# Petra_1.net
KiCad netlist of a schematic drawn in EAGLE
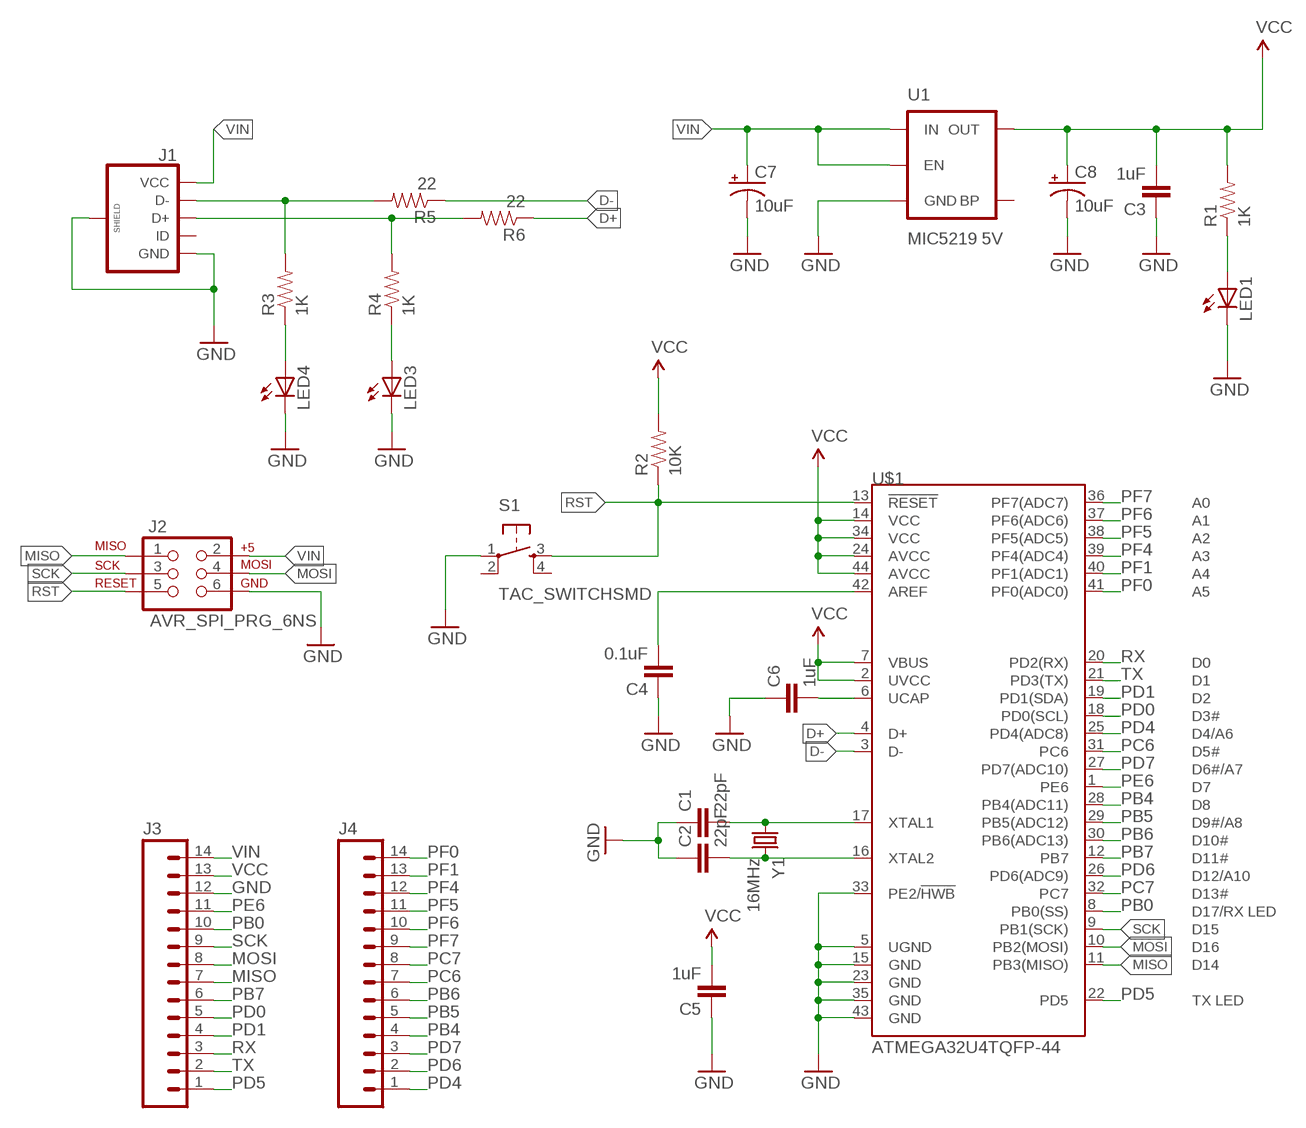
[diagram p0: schematic, sheet 1]

(export (version "E")
  (design (tool "Eeschema 10.0.6"))
  (components
    (comp (ref "C1")
      (value "22pF")
      (footprint "eagle-import:0402-CAP")
      (libsource (lib "eagle-import") (part "CAP0402-CAP"))
    )
    (comp (ref "C2")
      (value "22pF")
      (footprint "eagle-import:0402-CAP")
      (libsource (lib "eagle-import") (part "CAP0402-CAP"))
    )
    (comp (ref "C3")
      (value "1uF")
      (footprint "eagle-import:0402-CAP")
      (libsource (lib "eagle-import") (part "CAP0402-CAP"))
    )
    (comp (ref "C4")
      (value "0.1uF")
      (footprint "eagle-import:0402-CAP")
      (libsource (lib "eagle-import") (part "CAP0402-CAP"))
    )
    (comp (ref "C5")
      (value "1uF")
      (footprint "eagle-import:0402-CAP")
      (libsource (lib "eagle-import") (part "CAP0402-CAP"))
    )
    (comp (ref "C6")
      (value "1uF")
      (footprint "eagle-import:0402-CAP")
      (libsource (lib "eagle-import") (part "CAP0402-CAP"))
    )
    (comp (ref "C7")
      (value "10uF")
      (footprint "eagle-import:EIA3216")
      (libsource (lib "eagle-import") (part "CAP_POL1206"))
    )
    (comp (ref "C8")
      (value "10uF")
      (footprint "eagle-import:EIA3216")
      (libsource (lib "eagle-import") (part "CAP_POL1206"))
    )
    (comp (ref "J1")
      (value "USB_MICROB_PLUGCONN-11752")
      (footprint "eagle-import:USB-B-MICRO-SMD_V03")
      (libsource (lib "eagle-import") (part "USB_MICROB_PLUGCONN-11752"))
    )
    (comp (ref "J2")
      (value "AVR_SPI_PRG_6NS")
      (footprint "eagle-import:2X3-NS")
      (libsource (lib "eagle-import") (part "AVR_SPI_PRG_6NS"))
    )
    (comp (ref "J3")
      (value "M14")
      (footprint "eagle-import:1X14")
      (libsource (lib "eagle-import") (part "M14"))
    )
    (comp (ref "J4")
      (value "M14")
      (footprint "eagle-import:1X14")
      (libsource (lib "eagle-import") (part "M14"))
    )
    (comp (ref "LED1")
      (value "LEDCHIP-LED0805")
      (footprint "eagle-import:CHIP-LED0805")
      (libsource (lib "eagle-import") (part "LEDCHIP-LED0805"))
    )
    (comp (ref "LED3")
      (value "LEDCHIP-LED0805")
      (footprint "eagle-import:CHIP-LED0805")
      (libsource (lib "eagle-import") (part "LEDCHIP-LED0805"))
    )
    (comp (ref "LED4")
      (value "LEDCHIP-LED0805")
      (footprint "eagle-import:CHIP-LED0805")
      (libsource (lib "eagle-import") (part "LEDCHIP-LED0805"))
    )
    (comp (ref "R1")
      (value "1K")
      (footprint "eagle-import:0603-RES")
      (libsource (lib "eagle-import") (part "10KOHM-1/10W-1%(0603)0603"))
    )
    (comp (ref "R2")
      (value "10K")
      (footprint "eagle-import:0603-RES")
      (libsource (lib "eagle-import") (part "10KOHM-1/10W-1%(0603)0603"))
    )
    (comp (ref "R3")
      (value "1K")
      (footprint "eagle-import:0603-RES")
      (libsource (lib "eagle-import") (part "10KOHM-1/10W-1%(0603)0603"))
    )
    (comp (ref "R4")
      (value "1K")
      (footprint "eagle-import:0603-RES")
      (libsource (lib "eagle-import") (part "10KOHM-1/10W-1%(0603)0603"))
    )
    (comp (ref "R5")
      (value "22")
      (footprint "eagle-import:0603-RES")
      (libsource (lib "eagle-import") (part "10KOHM-1/10W-1%(0603)0603"))
    )
    (comp (ref "R6")
      (value "22")
      (footprint "eagle-import:0603-RES")
      (libsource (lib "eagle-import") (part "10KOHM-1/10W-1%(0603)0603"))
    )
    (comp (ref "S1")
      (value "TAC_SWITCHSMD")
      (footprint "eagle-import:TACTILE-SWITCH-SMD")
      (libsource (lib "eagle-import") (part "TAC_SWITCHSMD"))
    )
    (comp (ref "U$1")
      (value "ATMEGA32U4TQFP-44")
      (footprint "eagle-import:TQFP44")
      (libsource (lib "eagle-import") (part "ATMEGA32U4TQFP-44"))
    )
    (comp (ref "U1")
      (value "MIC5219 5V")
      (footprint "eagle-import:SOT23-5")
      (libsource (lib "eagle-import") (part "V_REG_MIC52195V"))
    )
    (comp (ref "Y1")
      (value "16MHz")
      (footprint "eagle-import:CRYSTAL-SMD-5X3")
      (libsource (lib "eagle-import") (part "CRYSTALCRYSTAL-SMD-5X3-16MHZ"))
    )
  )
  (nets
    (net (code "1") (name "/PB0") (class "Default")
      (node (ref "J3") (pin "10") (pinfunction "10_10") (pintype "passive"))
      (node (ref "U$1") (pin "8") (pinfunction "PB0(SS)_8") (pintype "bidirectional"))
    )
    (net (code "2") (name "/PB4") (class "Default")
      (node (ref "J4") (pin "4") (pinfunction "4_4") (pintype "passive"))
      (node (ref "U$1") (pin "28") (pinfunction "PB4(ADC11)_28") (pintype "bidirectional"))
    )
    (net (code "3") (name "/PB5") (class "Default")
      (node (ref "J4") (pin "5") (pinfunction "5_5") (pintype "passive"))
      (node (ref "U$1") (pin "29") (pinfunction "PB5(ADC12)_29") (pintype "bidirectional"))
    )
    (net (code "4") (name "/PB6") (class "Default")
      (node (ref "J4") (pin "6") (pinfunction "6_6") (pintype "passive"))
      (node (ref "U$1") (pin "30") (pinfunction "PB6(ADC13)_30") (pintype "bidirectional"))
    )
    (net (code "5") (name "/PB7") (class "Default")
      (node (ref "J3") (pin "6") (pinfunction "6_6") (pintype "passive"))
      (node (ref "U$1") (pin "12") (pinfunction "PB7_12") (pintype "bidirectional"))
    )
    (net (code "6") (name "/PC6") (class "Default")
      (node (ref "J4") (pin "7") (pinfunction "7_7") (pintype "passive"))
      (node (ref "U$1") (pin "31") (pinfunction "PC6_31") (pintype "bidirectional"))
    )
    (net (code "7") (name "/PC7") (class "Default")
      (node (ref "J4") (pin "8") (pinfunction "8_8") (pintype "passive"))
      (node (ref "U$1") (pin "32") (pinfunction "PC7_32") (pintype "bidirectional"))
    )
    (net (code "8") (name "/PD0") (class "Default")
      (node (ref "J3") (pin "5") (pinfunction "5_5") (pintype "passive"))
      (node (ref "U$1") (pin "18") (pinfunction "PD0(SCL)_18") (pintype "bidirectional"))
    )
    (net (code "9") (name "/PD1") (class "Default")
      (node (ref "J3") (pin "4") (pinfunction "4_4") (pintype "passive"))
      (node (ref "U$1") (pin "19") (pinfunction "PD1(SDA)_19") (pintype "bidirectional"))
    )
    (net (code "10") (name "/PD4") (class "Default")
      (node (ref "J4") (pin "1") (pinfunction "1_1") (pintype "passive"))
      (node (ref "U$1") (pin "25") (pinfunction "PD4(ADC8)_25") (pintype "bidirectional"))
    )
    (net (code "11") (name "/PD5") (class "Default")
      (node (ref "J3") (pin "1") (pinfunction "1_1") (pintype "passive"))
      (node (ref "U$1") (pin "22") (pinfunction "PD5_22") (pintype "bidirectional"))
    )
    (net (code "12") (name "/PD6") (class "Default")
      (node (ref "J4") (pin "2") (pinfunction "2_2") (pintype "passive"))
      (node (ref "U$1") (pin "26") (pinfunction "PD6(ADC9)_26") (pintype "bidirectional"))
    )
    (net (code "13") (name "/PD7") (class "Default")
      (node (ref "J4") (pin "3") (pinfunction "3_3") (pintype "passive"))
      (node (ref "U$1") (pin "27") (pinfunction "PD7(ADC10)_27") (pintype "bidirectional"))
    )
    (net (code "14") (name "/PE6") (class "Default")
      (node (ref "J3") (pin "11") (pinfunction "11_11") (pintype "passive"))
      (node (ref "U$1") (pin "1") (pinfunction "PE6_1") (pintype "bidirectional"))
    )
    (net (code "15") (name "/PF0") (class "Default")
      (node (ref "J4") (pin "14") (pinfunction "14_14") (pintype "passive"))
      (node (ref "U$1") (pin "41") (pinfunction "PF0(ADC0)_41") (pintype "bidirectional"))
    )
    (net (code "16") (name "/PF1") (class "Default")
      (node (ref "J4") (pin "13") (pinfunction "13_13") (pintype "passive"))
      (node (ref "U$1") (pin "40") (pinfunction "PF1(ADC1)_40") (pintype "bidirectional"))
    )
    (net (code "17") (name "/PF4") (class "Default")
      (node (ref "J4") (pin "12") (pinfunction "12_12") (pintype "passive"))
      (node (ref "U$1") (pin "39") (pinfunction "PF4(ADC4)_39") (pintype "bidirectional"))
    )
    (net (code "18") (name "/PF5") (class "Default")
      (node (ref "J4") (pin "11") (pinfunction "11_11") (pintype "passive"))
      (node (ref "U$1") (pin "38") (pinfunction "PF5(ADC5)_38") (pintype "bidirectional"))
    )
    (net (code "19") (name "/PF6") (class "Default")
      (node (ref "J4") (pin "10") (pinfunction "10_10") (pintype "passive"))
      (node (ref "U$1") (pin "37") (pinfunction "PF6(ADC6)_37") (pintype "bidirectional"))
    )
    (net (code "20") (name "/PF7") (class "Default")
      (node (ref "J4") (pin "9") (pinfunction "9_9") (pintype "passive"))
      (node (ref "U$1") (pin "36") (pinfunction "PF7(ADC7)_36") (pintype "bidirectional"))
    )
    (net (code "21") (name "/RX") (class "Default")
      (node (ref "J3") (pin "3") (pinfunction "3_3") (pintype "passive"))
      (node (ref "U$1") (pin "20") (pinfunction "PD2(RX)_20") (pintype "bidirectional"))
    )
    (net (code "22") (name "/TX") (class "Default")
      (node (ref "J3") (pin "2") (pinfunction "2_2") (pintype "passive"))
      (node (ref "U$1") (pin "21") (pinfunction "PD3(TX)_21") (pintype "bidirectional"))
    )
    (net (code "23") (name "D+") (class "Default")
      (node (ref "R6") (pin "1") (pinfunction "1_1") (pintype "passive"))
      (node (ref "U$1") (pin "4") (pinfunction "D+_4") (pintype "bidirectional"))
    )
    (net (code "24") (name "D-") (class "Default")
      (node (ref "R5") (pin "1") (pinfunction "1_1") (pintype "passive"))
      (node (ref "U$1") (pin "3") (pinfunction "D-_3") (pintype "bidirectional"))
    )
    (net (code "25") (name "GND") (class "Default")
      (node (ref "C1") (pin "1") (pinfunction "1_1") (pintype "passive"))
      (node (ref "C2") (pin "1") (pinfunction "1_1") (pintype "passive"))
      (node (ref "C3") (pin "1") (pinfunction "1_1") (pintype "passive"))
      (node (ref "C4") (pin "1") (pinfunction "1_1") (pintype "passive"))
      (node (ref "C5") (pin "1") (pinfunction "1_1") (pintype "passive"))
      (node (ref "C6") (pin "1") (pinfunction "1_1") (pintype "passive"))
      (node (ref "C7") (pin "C") (pinfunction "-_C") (pintype "passive"))
      (node (ref "C8") (pin "C") (pinfunction "-_C") (pintype "passive"))
      (node (ref "J1") (pin "GND") (pinfunction "GND_GND") (pintype "bidirectional"))
      (node (ref "J1") (pin "SHIELD1") (pinfunction "SHIELD_SHIELD1") (pintype "bidirectional"))
      (node (ref "J1") (pin "SHIELD2") (pinfunction "SHIELD_SHIELD2") (pintype "bidirectional"))
      (node (ref "J1") (pin "SHIELD3") (pinfunction "SHIELD_SHIELD3") (pintype "bidirectional"))
      (node (ref "J2") (pin "6") (pinfunction "6_6") (pintype "passive"))
      (node (ref "J3") (pin "12") (pinfunction "12_12") (pintype "passive"))
      (node (ref "LED1") (pin "C") (pinfunction "C_C") (pintype "passive"))
      (node (ref "LED3") (pin "C") (pinfunction "C_C") (pintype "passive"))
      (node (ref "LED4") (pin "C") (pinfunction "C_C") (pintype "passive"))
      (node (ref "S1") (pin "1") (pinfunction "1_1") (pintype "passive"))
      (node (ref "U$1") (pin "15") (pinfunction "GND_15") (pintype "bidirectional"))
      (node (ref "U$1") (pin "23") (pinfunction "GND_23") (pintype "bidirectional"))
      (node (ref "U$1") (pin "33") (pinfunction "PE2/~{HWB}_33") (pintype "bidirectional"))
      (node (ref "U$1") (pin "35") (pinfunction "GND_35") (pintype "bidirectional"))
      (node (ref "U$1") (pin "43") (pinfunction "GND_43") (pintype "bidirectional"))
      (node (ref "U$1") (pin "5") (pinfunction "UGND_5") (pintype "bidirectional"))
      (node (ref "U1") (pin "2") (pinfunction "GND_2") (pintype "input"))
    )
    (net (code "26") (name "MISO") (class "Default")
      (node (ref "J2") (pin "1") (pinfunction "1_1") (pintype "passive"))
      (node (ref "J3") (pin "7") (pinfunction "7_7") (pintype "passive"))
      (node (ref "U$1") (pin "11") (pinfunction "PB3(MISO)_11") (pintype "bidirectional"))
    )
    (net (code "27") (name "MOSI") (class "Default")
      (node (ref "J2") (pin "4") (pinfunction "4_4") (pintype "passive"))
      (node (ref "J3") (pin "8") (pinfunction "8_8") (pintype "passive"))
      (node (ref "U$1") (pin "10") (pinfunction "PB2(MOSI)_10") (pintype "bidirectional"))
    )
    (net (code "28") (name "Net-(J1-PadD+)") (class "Default")
      (node (ref "J1") (pin "D+") (pinfunction "D+_D+") (pintype "bidirectional"))
      (node (ref "R4") (pin "2") (pinfunction "2_2") (pintype "passive"))
      (node (ref "R6") (pin "2") (pinfunction "2_2") (pintype "passive"))
    )
    (net (code "29") (name "Net-(J1-PadD-)") (class "Default")
      (node (ref "J1") (pin "D-") (pinfunction "D-_D-") (pintype "bidirectional"))
      (node (ref "R3") (pin "2") (pinfunction "2_2") (pintype "passive"))
      (node (ref "R5") (pin "2") (pinfunction "2_2") (pintype "passive"))
    )
    (net (code "30") (name "Net-(LED1-PadA)") (class "Default")
      (node (ref "LED1") (pin "A") (pinfunction "A_A") (pintype "passive"))
      (node (ref "R1") (pin "1") (pinfunction "1_1") (pintype "passive"))
    )
    (net (code "31") (name "Net-(LED3-PadA)") (class "Default")
      (node (ref "LED3") (pin "A") (pinfunction "A_A") (pintype "passive"))
      (node (ref "R4") (pin "1") (pinfunction "1_1") (pintype "passive"))
    )
    (net (code "32") (name "Net-(LED4-PadA)") (class "Default")
      (node (ref "LED4") (pin "A") (pinfunction "A_A") (pintype "passive"))
      (node (ref "R3") (pin "1") (pinfunction "1_1") (pintype "passive"))
    )
    (net (code "33") (name "Net-(U$1-AREF)") (class "Default")
      (node (ref "C4") (pin "2") (pinfunction "2_2") (pintype "passive"))
      (node (ref "U$1") (pin "42") (pinfunction "AREF_42") (pintype "bidirectional"))
    )
    (net (code "34") (name "Net-(U$1-UCAP)") (class "Default")
      (node (ref "C6") (pin "2") (pinfunction "2_2") (pintype "passive"))
      (node (ref "U$1") (pin "6") (pinfunction "UCAP_6") (pintype "bidirectional"))
    )
    (net (code "35") (name "Net-(U$1-XTAL1)") (class "Default")
      (node (ref "C1") (pin "2") (pinfunction "2_2") (pintype "passive"))
      (node (ref "U$1") (pin "17") (pinfunction "XTAL1_17") (pintype "bidirectional"))
      (node (ref "Y1") (pin "1") (pinfunction "1_1") (pintype "passive"))
    )
    (net (code "36") (name "Net-(U$1-XTAL2)") (class "Default")
      (node (ref "C2") (pin "2") (pinfunction "2_2") (pintype "passive"))
      (node (ref "U$1") (pin "16") (pinfunction "XTAL2_16") (pintype "bidirectional"))
      (node (ref "Y1") (pin "3") (pinfunction "2_3") (pintype "passive"))
    )
    (net (code "37") (name "RST") (class "Default")
      (node (ref "J2") (pin "5") (pinfunction "5_5") (pintype "passive"))
      (node (ref "R2") (pin "1") (pinfunction "1_1") (pintype "passive"))
      (node (ref "S1") (pin "3") (pinfunction "3_3") (pintype "passive"))
      (node (ref "U$1") (pin "13") (pinfunction "~{RESET}_13") (pintype "bidirectional"))
    )
    (net (code "38") (name "SCK") (class "Default")
      (node (ref "J2") (pin "3") (pinfunction "3_3") (pintype "passive"))
      (node (ref "J3") (pin "9") (pinfunction "9_9") (pintype "passive"))
      (node (ref "U$1") (pin "9") (pinfunction "PB1(SCK)_9") (pintype "bidirectional"))
    )
    (net (code "39") (name "VCC") (class "Default")
      (node (ref "C3") (pin "2") (pinfunction "2_2") (pintype "passive"))
      (node (ref "C5") (pin "2") (pinfunction "2_2") (pintype "passive"))
      (node (ref "C8") (pin "A") (pinfunction "+_A") (pintype "passive"))
      (node (ref "J3") (pin "13") (pinfunction "13_13") (pintype "passive"))
      (node (ref "R1") (pin "2") (pinfunction "2_2") (pintype "passive"))
      (node (ref "R2") (pin "2") (pinfunction "2_2") (pintype "passive"))
      (node (ref "U$1") (pin "14") (pinfunction "VCC_14") (pintype "bidirectional"))
      (node (ref "U$1") (pin "2") (pinfunction "UVCC_2") (pintype "bidirectional"))
      (node (ref "U$1") (pin "24") (pinfunction "AVCC_24") (pintype "bidirectional"))
      (node (ref "U$1") (pin "34") (pinfunction "VCC_34") (pintype "bidirectional"))
      (node (ref "U$1") (pin "44") (pinfunction "AVCC_44") (pintype "bidirectional"))
      (node (ref "U$1") (pin "7") (pinfunction "VBUS_7") (pintype "bidirectional"))
      (node (ref "U1") (pin "5") (pinfunction "OUT_5") (pintype "passive"))
    )
    (net (code "40") (name "VIN") (class "Default")
      (node (ref "C7") (pin "A") (pinfunction "+_A") (pintype "passive"))
      (node (ref "J1") (pin "VBUS") (pinfunction "VCC_VBUS") (pintype "bidirectional"))
      (node (ref "J2") (pin "2") (pinfunction "2_2") (pintype "passive"))
      (node (ref "J3") (pin "14") (pinfunction "14_14") (pintype "passive"))
      (node (ref "U1") (pin "1") (pinfunction "IN_1") (pintype "input"))
      (node (ref "U1") (pin "3") (pinfunction "EN_3") (pintype "input"))
    )
    (net (code "41") (name "unconnected-(J1-PadID)") (class "Default")
      (node (ref "J1") (pin "ID") (pinfunction "ID_ID") (pintype "bidirectional"))
    )
    (net (code "42") (name "unconnected-(S1-Pad2)") (class "Default")
      (node (ref "S1") (pin "2") (pinfunction "2_2") (pintype "passive"))
    )
    (net (code "43") (name "unconnected-(S1-Pad4)") (class "Default")
      (node (ref "S1") (pin "4") (pinfunction "4_4") (pintype "passive"))
    )
    (net (code "44") (name "unconnected-(U1-BP-Pad4)") (class "Default")
      (node (ref "U1") (pin "4") (pinfunction "BP_4") (pintype "input"))
    )
  )
)
